# zerg_mc.net
KiCad netlist of a schematic drawn in EAGLE
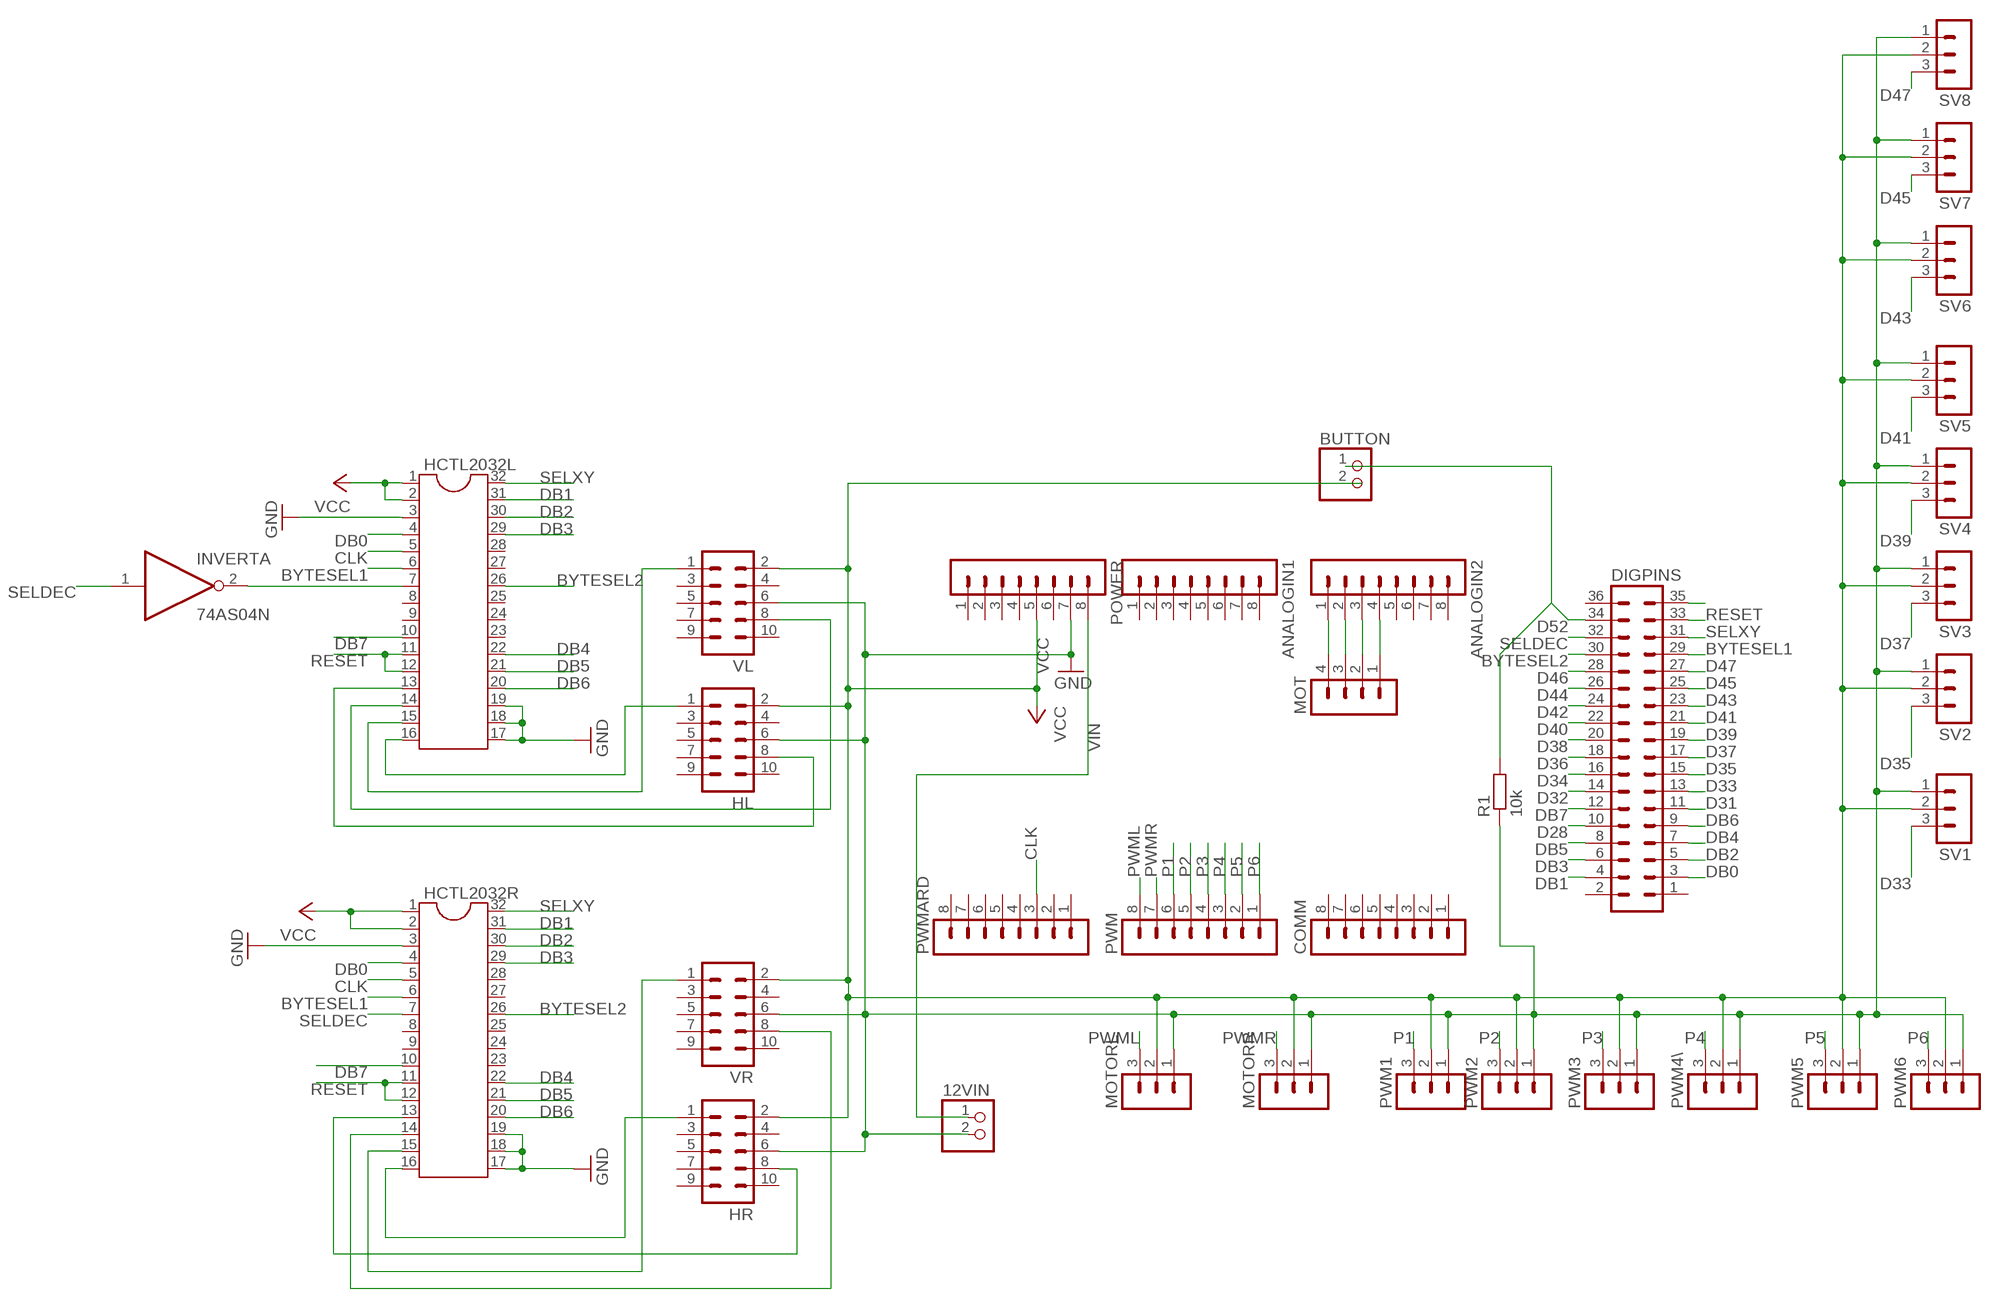
[diagram p0: schematic, sheet 1]

(export (version "E")
  (design (tool "Eeschema 10.0.6"))
  (components
    (comp (ref "12VIN")
      (value "PINHD-1X2")
      (footprint "eagle-import:1X02")
      (libsource (lib "eagle-import") (part "PINHD-1X2"))
    )
    (comp (ref "ANALOGIN1")
      (value "MA08-1")
      (footprint "eagle-import:MA08-1")
      (libsource (lib "eagle-import") (part "MA08-1"))
    )
    (comp (ref "ANALOGIN2")
      (value "MA08-1")
      (footprint "eagle-import:MA08-1")
      (libsource (lib "eagle-import") (part "MA08-1"))
    )
    (comp (ref "BUTTON")
      (value "PINHD-1X2")
      (footprint "eagle-import:1X02")
      (libsource (lib "eagle-import") (part "PINHD-1X2"))
    )
    (comp (ref "COMM")
      (value "MA08-1")
      (footprint "eagle-import:MA08-1")
      (libsource (lib "eagle-import") (part "MA08-1"))
    )
    (comp (ref "DIGPINS")
      (value "MA18-2")
      (footprint "eagle-import:MA18-2")
      (libsource (lib "eagle-import") (part "MA18-2"))
    )
    (comp (ref "HCTL2032L")
      (value "DIL32")
      (footprint "eagle-import:DIL32")
      (libsource (lib "eagle-import") (part "DIL32"))
    )
    (comp (ref "HCTL2032R")
      (value "DIL32")
      (footprint "eagle-import:DIL32")
      (libsource (lib "eagle-import") (part "DIL32"))
    )
    (comp (ref "HL")
      (value "MA05-2")
      (footprint "eagle-import:MA05-2")
      (libsource (lib "eagle-import") (part "MA05-2"))
    )
    (comp (ref "HR")
      (value "MA05-2")
      (footprint "eagle-import:MA05-2")
      (libsource (lib "eagle-import") (part "MA05-2"))
    )
    (comp (ref "INVERT")
      (value "74AS04N")
      (footprint "eagle-import:DIL14")
      (libsource (lib "eagle-import") (part "7404NAS"))
    )
    (comp (ref "MOT")
      (value "MA04-1")
      (footprint "eagle-import:MA04-1")
      (libsource (lib "eagle-import") (part "MA04-1"))
    )
    (comp (ref "MOTORL")
      (value "MA03-1")
      (footprint "eagle-import:MA03-1")
      (libsource (lib "eagle-import") (part "MA03-1"))
    )
    (comp (ref "MOTORR")
      (value "MA03-1")
      (footprint "eagle-import:MA03-1")
      (libsource (lib "eagle-import") (part "MA03-1"))
    )
    (comp (ref "POWER")
      (value "MA08-1")
      (footprint "eagle-import:MA08-1")
      (libsource (lib "eagle-import") (part "MA08-1"))
    )
    (comp (ref "PWM")
      (value "MA08-1")
      (footprint "eagle-import:MA08-1")
      (libsource (lib "eagle-import") (part "MA08-1"))
    )
    (comp (ref "PWM1")
      (value "MA03-1")
      (footprint "eagle-import:MA03-1")
      (libsource (lib "eagle-import") (part "MA03-1"))
    )
    (comp (ref "PWM2")
      (value "MA03-1")
      (footprint "eagle-import:MA03-1")
      (libsource (lib "eagle-import") (part "MA03-1"))
    )
    (comp (ref "PWM3")
      (value "MA03-1")
      (footprint "eagle-import:MA03-1")
      (libsource (lib "eagle-import") (part "MA03-1"))
    )
    (comp (ref "PWM4\\")
      (value "MA03-1")
      (footprint "eagle-import:MA03-1")
      (libsource (lib "eagle-import") (part "MA03-1"))
    )
    (comp (ref "PWM5")
      (value "MA03-1")
      (footprint "eagle-import:MA03-1")
      (libsource (lib "eagle-import") (part "MA03-1"))
    )
    (comp (ref "PWM6")
      (value "MA03-1")
      (footprint "eagle-import:MA03-1")
      (libsource (lib "eagle-import") (part "MA03-1"))
    )
    (comp (ref "PWMARD")
      (value "MA08-1")
      (footprint "eagle-import:MA08-1")
      (libsource (lib "eagle-import") (part "MA08-1"))
    )
    (comp (ref "R1")
      (value "10k")
      (footprint "eagle-import:0207_10")
      (libsource (lib "eagle-import") (part "R-EU_0207/10"))
    )
    (comp (ref "SV1")
      (value "MA03-1")
      (footprint "eagle-import:MA03-1")
      (libsource (lib "eagle-import") (part "MA03-1"))
    )
    (comp (ref "SV2")
      (value "MA03-1")
      (footprint "eagle-import:MA03-1")
      (libsource (lib "eagle-import") (part "MA03-1"))
    )
    (comp (ref "SV3")
      (value "MA03-1")
      (footprint "eagle-import:MA03-1")
      (libsource (lib "eagle-import") (part "MA03-1"))
    )
    (comp (ref "SV4")
      (value "MA03-1")
      (footprint "eagle-import:MA03-1")
      (libsource (lib "eagle-import") (part "MA03-1"))
    )
    (comp (ref "SV5")
      (value "MA03-1")
      (footprint "eagle-import:MA03-1")
      (libsource (lib "eagle-import") (part "MA03-1"))
    )
    (comp (ref "SV6")
      (value "MA03-1")
      (footprint "eagle-import:MA03-1")
      (libsource (lib "eagle-import") (part "MA03-1"))
    )
    (comp (ref "SV7")
      (value "MA03-1")
      (footprint "eagle-import:MA03-1")
      (libsource (lib "eagle-import") (part "MA03-1"))
    )
    (comp (ref "SV8")
      (value "MA03-1")
      (footprint "eagle-import:MA03-1")
      (libsource (lib "eagle-import") (part "MA03-1"))
    )
    (comp (ref "VL")
      (value "MA05-2")
      (footprint "eagle-import:MA05-2")
      (libsource (lib "eagle-import") (part "MA05-2"))
    )
    (comp (ref "VR")
      (value "MA05-2")
      (footprint "eagle-import:MA05-2")
      (libsource (lib "eagle-import") (part "MA05-2"))
    )
  )
  (nets
    (net (code "1") (name "/BYTESEL1") (class "Default")
      (node (ref "DIGPINS") (pin "29") (pinfunction "29_29") (pintype "passive"))
      (node (ref "HCTL2032L") (pin "6") (pinfunction "6_6") (pintype "passive"))
      (node (ref "HCTL2032R") (pin "6") (pinfunction "6_6") (pintype "passive"))
    )
    (net (code "2") (name "/BYTESEL2") (class "Default")
      (node (ref "DIGPINS") (pin "30") (pinfunction "30_30") (pintype "passive"))
      (node (ref "HCTL2032L") (pin "26") (pinfunction "26_26") (pintype "passive"))
      (node (ref "HCTL2032R") (pin "26") (pinfunction "26_26") (pintype "passive"))
    )
    (net (code "3") (name "/CLK") (class "Default")
      (node (ref "HCTL2032L") (pin "5") (pinfunction "5_5") (pintype "passive"))
      (node (ref "HCTL2032R") (pin "5") (pinfunction "5_5") (pintype "passive"))
      (node (ref "PWMARD") (pin "3") (pinfunction "3_3") (pintype "passive"))
    )
    (net (code "4") (name "/D28") (class "Default")
      (node (ref "DIGPINS") (pin "10") (pinfunction "10_10") (pintype "passive"))
    )
    (net (code "5") (name "/D31") (class "Default")
      (node (ref "DIGPINS") (pin "11") (pinfunction "11_11") (pintype "passive"))
    )
    (net (code "6") (name "/D32") (class "Default")
      (node (ref "DIGPINS") (pin "14") (pinfunction "14_14") (pintype "passive"))
    )
    (net (code "7") (name "/D33") (class "Default")
      (node (ref "DIGPINS") (pin "13") (pinfunction "13_13") (pintype "passive"))
      (node (ref "SV1") (pin "3") (pinfunction "3_3") (pintype "passive"))
    )
    (net (code "8") (name "/D34") (class "Default")
      (node (ref "DIGPINS") (pin "16") (pinfunction "16_16") (pintype "passive"))
    )
    (net (code "9") (name "/D35") (class "Default")
      (node (ref "DIGPINS") (pin "15") (pinfunction "15_15") (pintype "passive"))
      (node (ref "SV2") (pin "3") (pinfunction "3_3") (pintype "passive"))
    )
    (net (code "10") (name "/D36") (class "Default")
      (node (ref "DIGPINS") (pin "18") (pinfunction "18_18") (pintype "passive"))
    )
    (net (code "11") (name "/D37") (class "Default")
      (node (ref "DIGPINS") (pin "17") (pinfunction "17_17") (pintype "passive"))
      (node (ref "SV3") (pin "3") (pinfunction "3_3") (pintype "passive"))
    )
    (net (code "12") (name "/D38") (class "Default")
      (node (ref "DIGPINS") (pin "20") (pinfunction "20_20") (pintype "passive"))
    )
    (net (code "13") (name "/D39") (class "Default")
      (node (ref "DIGPINS") (pin "19") (pinfunction "19_19") (pintype "passive"))
      (node (ref "SV4") (pin "3") (pinfunction "3_3") (pintype "passive"))
    )
    (net (code "14") (name "/D40") (class "Default")
      (node (ref "DIGPINS") (pin "22") (pinfunction "22_22") (pintype "passive"))
    )
    (net (code "15") (name "/D41") (class "Default")
      (node (ref "DIGPINS") (pin "21") (pinfunction "21_21") (pintype "passive"))
      (node (ref "SV5") (pin "3") (pinfunction "3_3") (pintype "passive"))
    )
    (net (code "16") (name "/D42") (class "Default")
      (node (ref "DIGPINS") (pin "24") (pinfunction "24_24") (pintype "passive"))
    )
    (net (code "17") (name "/D43") (class "Default")
      (node (ref "DIGPINS") (pin "23") (pinfunction "23_23") (pintype "passive"))
      (node (ref "SV6") (pin "3") (pinfunction "3_3") (pintype "passive"))
    )
    (net (code "18") (name "/D44") (class "Default")
      (node (ref "DIGPINS") (pin "26") (pinfunction "26_26") (pintype "passive"))
    )
    (net (code "19") (name "/D45") (class "Default")
      (node (ref "DIGPINS") (pin "25") (pinfunction "25_25") (pintype "passive"))
      (node (ref "SV7") (pin "3") (pinfunction "3_3") (pintype "passive"))
    )
    (net (code "20") (name "/D46") (class "Default")
      (node (ref "DIGPINS") (pin "28") (pinfunction "28_28") (pintype "passive"))
    )
    (net (code "21") (name "/D47") (class "Default")
      (node (ref "DIGPINS") (pin "27") (pinfunction "27_27") (pintype "passive"))
      (node (ref "SV8") (pin "3") (pinfunction "3_3") (pintype "passive"))
    )
    (net (code "22") (name "/D52") (class "Default")
      (node (ref "BUTTON") (pin "1") (pinfunction "1_1") (pintype "passive"))
      (node (ref "DIGPINS") (pin "34") (pinfunction "34_34") (pintype "passive"))
      (node (ref "R1") (pin "2") (pinfunction "2_2") (pintype "passive"))
    )
    (net (code "23") (name "/DB0") (class "Default")
      (node (ref "DIGPINS") (pin "3") (pinfunction "3_3") (pintype "passive"))
      (node (ref "HCTL2032L") (pin "4") (pinfunction "4_4") (pintype "passive"))
      (node (ref "HCTL2032R") (pin "4") (pinfunction "4_4") (pintype "passive"))
    )
    (net (code "24") (name "/DB1") (class "Default")
      (node (ref "DIGPINS") (pin "4") (pinfunction "4_4") (pintype "passive"))
      (node (ref "HCTL2032L") (pin "31") (pinfunction "31_31") (pintype "passive"))
      (node (ref "HCTL2032R") (pin "31") (pinfunction "31_31") (pintype "passive"))
    )
    (net (code "25") (name "/DB2") (class "Default")
      (node (ref "DIGPINS") (pin "5") (pinfunction "5_5") (pintype "passive"))
      (node (ref "HCTL2032L") (pin "30") (pinfunction "30_30") (pintype "passive"))
      (node (ref "HCTL2032R") (pin "30") (pinfunction "30_30") (pintype "passive"))
    )
    (net (code "26") (name "/DB3") (class "Default")
      (node (ref "DIGPINS") (pin "6") (pinfunction "6_6") (pintype "passive"))
      (node (ref "HCTL2032L") (pin "29") (pinfunction "29_29") (pintype "passive"))
      (node (ref "HCTL2032R") (pin "29") (pinfunction "29_29") (pintype "passive"))
    )
    (net (code "27") (name "/DB4") (class "Default")
      (node (ref "DIGPINS") (pin "7") (pinfunction "7_7") (pintype "passive"))
      (node (ref "HCTL2032L") (pin "22") (pinfunction "22_22") (pintype "passive"))
      (node (ref "HCTL2032R") (pin "22") (pinfunction "22_22") (pintype "passive"))
    )
    (net (code "28") (name "/DB5") (class "Default")
      (node (ref "DIGPINS") (pin "8") (pinfunction "8_8") (pintype "passive"))
      (node (ref "HCTL2032L") (pin "21") (pinfunction "21_21") (pintype "passive"))
      (node (ref "HCTL2032R") (pin "21") (pinfunction "21_21") (pintype "passive"))
    )
    (net (code "29") (name "/DB6") (class "Default")
      (node (ref "DIGPINS") (pin "9") (pinfunction "9_9") (pintype "passive"))
      (node (ref "HCTL2032L") (pin "20") (pinfunction "20_20") (pintype "passive"))
      (node (ref "HCTL2032R") (pin "20") (pinfunction "20_20") (pintype "passive"))
    )
    (net (code "30") (name "/DB7") (class "Default")
      (node (ref "DIGPINS") (pin "12") (pinfunction "12_12") (pintype "passive"))
      (node (ref "HCTL2032L") (pin "10") (pinfunction "10_10") (pintype "passive"))
      (node (ref "HCTL2032R") (pin "10") (pinfunction "10_10") (pintype "passive"))
    )
    (net (code "31") (name "/P1") (class "Default")
      (node (ref "PWM") (pin "6") (pinfunction "6_6") (pintype "passive"))
      (node (ref "PWM1") (pin "3") (pinfunction "3_3") (pintype "passive"))
    )
    (net (code "32") (name "/P2") (class "Default")
      (node (ref "PWM") (pin "5") (pinfunction "5_5") (pintype "passive"))
      (node (ref "PWM2") (pin "3") (pinfunction "3_3") (pintype "passive"))
    )
    (net (code "33") (name "/P3") (class "Default")
      (node (ref "PWM") (pin "4") (pinfunction "4_4") (pintype "passive"))
      (node (ref "PWM3") (pin "3") (pinfunction "3_3") (pintype "passive"))
    )
    (net (code "34") (name "/P4") (class "Default")
      (node (ref "PWM") (pin "3") (pinfunction "3_3") (pintype "passive"))
      (node (ref "PWM4\\") (pin "3") (pinfunction "3_3") (pintype "passive"))
    )
    (net (code "35") (name "/P5") (class "Default")
      (node (ref "PWM") (pin "2") (pinfunction "2_2") (pintype "passive"))
      (node (ref "PWM5") (pin "3") (pinfunction "3_3") (pintype "passive"))
    )
    (net (code "36") (name "/P6") (class "Default")
      (node (ref "PWM") (pin "1") (pinfunction "1_1") (pintype "passive"))
      (node (ref "PWM6") (pin "3") (pinfunction "3_3") (pintype "passive"))
    )
    (net (code "37") (name "/PWML") (class "Default")
      (node (ref "MOTORL") (pin "3") (pinfunction "3_3") (pintype "passive"))
      (node (ref "PWM") (pin "8") (pinfunction "8_8") (pintype "passive"))
    )
    (net (code "38") (name "/PWMR") (class "Default")
      (node (ref "MOTORR") (pin "3") (pinfunction "3_3") (pintype "passive"))
      (node (ref "PWM") (pin "7") (pinfunction "7_7") (pintype "passive"))
    )
    (net (code "39") (name "/RESET") (class "Default")
      (node (ref "DIGPINS") (pin "33") (pinfunction "33_33") (pintype "passive"))
      (node (ref "HCTL2032L") (pin "11") (pinfunction "11_11") (pintype "passive"))
      (node (ref "HCTL2032L") (pin "12") (pinfunction "12_12") (pintype "passive"))
      (node (ref "HCTL2032R") (pin "11") (pinfunction "11_11") (pintype "passive"))
      (node (ref "HCTL2032R") (pin "12") (pinfunction "12_12") (pintype "passive"))
    )
    (net (code "40") (name "/SELDEC") (class "Default")
      (node (ref "DIGPINS") (pin "32") (pinfunction "32_32") (pintype "passive"))
      (node (ref "HCTL2032R") (pin "7") (pinfunction "7_7") (pintype "passive"))
      (node (ref "INVERT") (pin "1") (pinfunction "I_1") (pintype "input"))
    )
    (net (code "41") (name "/SELXY") (class "Default")
      (node (ref "DIGPINS") (pin "31") (pinfunction "31_31") (pintype "passive"))
      (node (ref "HCTL2032L") (pin "32") (pinfunction "32_32") (pintype "passive"))
      (node (ref "HCTL2032R") (pin "32") (pinfunction "32_32") (pintype "passive"))
    )
    (net (code "42") (name "/VIN") (class "Default")
      (node (ref "12VIN") (pin "1") (pinfunction "1_1") (pintype "passive"))
      (node (ref "POWER") (pin "8") (pinfunction "8_8") (pintype "passive"))
    )
    (net (code "43") (name "GND") (class "Default")
      (node (ref "12VIN") (pin "2") (pinfunction "2_2") (pintype "passive"))
      (node (ref "HCTL2032L") (pin "17") (pinfunction "17_17") (pintype "passive"))
      (node (ref "HCTL2032L") (pin "18") (pinfunction "18_18") (pintype "passive"))
      (node (ref "HCTL2032L") (pin "19") (pinfunction "19_19") (pintype "passive"))
      (node (ref "HCTL2032L") (pin "3") (pinfunction "3_3") (pintype "passive"))
      (node (ref "HCTL2032R") (pin "17") (pinfunction "17_17") (pintype "passive"))
      (node (ref "HCTL2032R") (pin "18") (pinfunction "18_18") (pintype "passive"))
      (node (ref "HCTL2032R") (pin "19") (pinfunction "19_19") (pintype "passive"))
      (node (ref "HCTL2032R") (pin "3") (pinfunction "3_3") (pintype "passive"))
      (node (ref "HL") (pin "6") (pinfunction "6_6") (pintype "passive"))
      (node (ref "HR") (pin "6") (pinfunction "6_6") (pintype "passive"))
      (node (ref "MOTORL") (pin "1") (pinfunction "1_1") (pintype "passive"))
      (node (ref "MOTORR") (pin "1") (pinfunction "1_1") (pintype "passive"))
      (node (ref "POWER") (pin "7") (pinfunction "7_7") (pintype "passive"))
      (node (ref "PWM1") (pin "1") (pinfunction "1_1") (pintype "passive"))
      (node (ref "PWM2") (pin "1") (pinfunction "1_1") (pintype "passive"))
      (node (ref "PWM3") (pin "1") (pinfunction "1_1") (pintype "passive"))
      (node (ref "PWM4\\") (pin "1") (pinfunction "1_1") (pintype "passive"))
      (node (ref "PWM5") (pin "1") (pinfunction "1_1") (pintype "passive"))
      (node (ref "PWM6") (pin "1") (pinfunction "1_1") (pintype "passive"))
      (node (ref "R1") (pin "1") (pinfunction "1_1") (pintype "passive"))
      (node (ref "SV1") (pin "1") (pinfunction "1_1") (pintype "passive"))
      (node (ref "SV2") (pin "1") (pinfunction "1_1") (pintype "passive"))
      (node (ref "SV3") (pin "1") (pinfunction "1_1") (pintype "passive"))
      (node (ref "SV4") (pin "1") (pinfunction "1_1") (pintype "passive"))
      (node (ref "SV5") (pin "1") (pinfunction "1_1") (pintype "passive"))
      (node (ref "SV6") (pin "1") (pinfunction "1_1") (pintype "passive"))
      (node (ref "SV7") (pin "1") (pinfunction "1_1") (pintype "passive"))
      (node (ref "SV8") (pin "1") (pinfunction "1_1") (pintype "passive"))
      (node (ref "VL") (pin "6") (pinfunction "6_6") (pintype "passive"))
      (node (ref "VR") (pin "6") (pinfunction "6_6") (pintype "passive"))
    )
    (net (code "44") (name "Net-(ANALOGIN2-Pad1)") (class "Default")
      (node (ref "ANALOGIN2") (pin "1") (pinfunction "1_1") (pintype "passive"))
      (node (ref "MOT") (pin "4") (pinfunction "4_4") (pintype "passive"))
    )
    (net (code "45") (name "Net-(ANALOGIN2-Pad2)") (class "Default")
      (node (ref "ANALOGIN2") (pin "2") (pinfunction "2_2") (pintype "passive"))
      (node (ref "MOT") (pin "3") (pinfunction "3_3") (pintype "passive"))
    )
    (net (code "46") (name "Net-(ANALOGIN2-Pad3)") (class "Default")
      (node (ref "ANALOGIN2") (pin "3") (pinfunction "3_3") (pintype "passive"))
      (node (ref "MOT") (pin "2") (pinfunction "2_2") (pintype "passive"))
    )
    (net (code "47") (name "Net-(ANALOGIN2-Pad4)") (class "Default")
      (node (ref "ANALOGIN2") (pin "4") (pinfunction "4_4") (pintype "passive"))
      (node (ref "MOT") (pin "1") (pinfunction "1_1") (pintype "passive"))
    )
    (net (code "48") (name "Net-(HCTL2032L-Pad13)") (class "Default")
      (node (ref "HCTL2032L") (pin "13") (pinfunction "13_13") (pintype "passive"))
      (node (ref "HL") (pin "8") (pinfunction "8_8") (pintype "passive"))
    )
    (net (code "49") (name "Net-(HCTL2032L-Pad14)") (class "Default")
      (node (ref "HCTL2032L") (pin "14") (pinfunction "14_14") (pintype "passive"))
      (node (ref "VL") (pin "8") (pinfunction "8_8") (pintype "passive"))
    )
    (net (code "50") (name "Net-(HCTL2032L-Pad15)") (class "Default")
      (node (ref "HCTL2032L") (pin "15") (pinfunction "15_15") (pintype "passive"))
      (node (ref "VL") (pin "1") (pinfunction "1_1") (pintype "passive"))
    )
    (net (code "51") (name "Net-(HCTL2032L-Pad16)") (class "Default")
      (node (ref "HCTL2032L") (pin "16") (pinfunction "16_16") (pintype "passive"))
      (node (ref "HL") (pin "1") (pinfunction "1_1") (pintype "passive"))
    )
    (net (code "52") (name "Net-(HCTL2032R-Pad13)") (class "Default")
      (node (ref "HCTL2032R") (pin "13") (pinfunction "13_13") (pintype "passive"))
      (node (ref "HR") (pin "8") (pinfunction "8_8") (pintype "passive"))
    )
    (net (code "53") (name "Net-(HCTL2032R-Pad14)") (class "Default")
      (node (ref "HCTL2032R") (pin "14") (pinfunction "14_14") (pintype "passive"))
      (node (ref "VR") (pin "8") (pinfunction "8_8") (pintype "passive"))
    )
    (net (code "54") (name "Net-(HCTL2032R-Pad15)") (class "Default")
      (node (ref "HCTL2032R") (pin "15") (pinfunction "15_15") (pintype "passive"))
      (node (ref "VR") (pin "1") (pinfunction "1_1") (pintype "passive"))
    )
    (net (code "55") (name "Net-(HCTL2032R-Pad16)") (class "Default")
      (node (ref "HCTL2032R") (pin "16") (pinfunction "16_16") (pintype "passive"))
      (node (ref "HR") (pin "1") (pinfunction "1_1") (pintype "passive"))
    )
    (net (code "56") (name "Net-(INVERTA-O)") (class "Default")
      (node (ref "HCTL2032L") (pin "7") (pinfunction "7_7") (pintype "passive"))
      (node (ref "INVERT") (pin "2") (pinfunction "O_2") (pintype "output"))
    )
    (net (code "57") (name "VCC") (class "Default")
      (node (ref "HCTL2032L") (pin "1") (pinfunction "1_1") (pintype "passive"))
      (node (ref "HCTL2032L") (pin "2") (pinfunction "2_2") (pintype "passive"))
      (node (ref "HCTL2032R") (pin "1") (pinfunction "1_1") (pintype "passive"))
      (node (ref "HCTL2032R") (pin "2") (pinfunction "2_2") (pintype "passive"))
      (node (ref "HL") (pin "2") (pinfunction "2_2") (pintype "passive"))
      (node (ref "HR") (pin "2") (pinfunction "2_2") (pintype "passive"))
      (node (ref "MOTORL") (pin "2") (pinfunction "2_2") (pintype "passive"))
      (node (ref "MOTORR") (pin "2") (pinfunction "2_2") (pintype "passive"))
      (node (ref "POWER") (pin "5") (pinfunction "5_5") (pintype "passive"))
      (node (ref "PWM1") (pin "2") (pinfunction "2_2") (pintype "passive"))
      (node (ref "PWM2") (pin "2") (pinfunction "2_2") (pintype "passive"))
      (node (ref "PWM3") (pin "2") (pinfunction "2_2") (pintype "passive"))
      (node (ref "PWM4\\") (pin "2") (pinfunction "2_2") (pintype "passive"))
      (node (ref "PWM5") (pin "2") (pinfunction "2_2") (pintype "passive"))
      (node (ref "PWM6") (pin "2") (pinfunction "2_2") (pintype "passive"))
      (node (ref "SV1") (pin "2") (pinfunction "2_2") (pintype "passive"))
      (node (ref "SV2") (pin "2") (pinfunction "2_2") (pintype "passive"))
      (node (ref "SV3") (pin "2") (pinfunction "2_2") (pintype "passive"))
      (node (ref "SV4") (pin "2") (pinfunction "2_2") (pintype "passive"))
      (node (ref "SV5") (pin "2") (pinfunction "2_2") (pintype "passive"))
      (node (ref "SV6") (pin "2") (pinfunction "2_2") (pintype "passive"))
      (node (ref "SV7") (pin "2") (pinfunction "2_2") (pintype "passive"))
      (node (ref "SV8") (pin "2") (pinfunction "2_2") (pintype "passive"))
      (node (ref "VL") (pin "2") (pinfunction "2_2") (pintype "passive"))
      (node (ref "VR") (pin "2") (pinfunction "2_2") (pintype "passive"))
    )
    (net (code "58") (name "unconnected-(ANALOGIN1-Pad1)") (class "Default")
      (node (ref "ANALOGIN1") (pin "1") (pinfunction "1_1") (pintype "passive"))
    )
    (net (code "59") (name "unconnected-(ANALOGIN1-Pad2)") (class "Default")
      (node (ref "ANALOGIN1") (pin "2") (pinfunction "2_2") (pintype "passive"))
    )
    (net (code "60") (name "unconnected-(ANALOGIN1-Pad3)") (class "Default")
      (node (ref "ANALOGIN1") (pin "3") (pinfunction "3_3") (pintype "passive"))
    )
    (net (code "61") (name "unconnected-(ANALOGIN1-Pad4)") (class "Default")
      (node (ref "ANALOGIN1") (pin "4") (pinfunction "4_4") (pintype "passive"))
    )
    (net (code "62") (name "unconnected-(ANALOGIN1-Pad5)") (class "Default")
      (node (ref "ANALOGIN1") (pin "5") (pinfunction "5_5") (pintype "passive"))
    )
    (net (code "63") (name "unconnected-(ANALOGIN1-Pad6)") (class "Default")
      (node (ref "ANALOGIN1") (pin "6") (pinfunction "6_6") (pintype "passive"))
    )
    (net (code "64") (name "unconnected-(ANALOGIN1-Pad7)") (class "Default")
      (node (ref "ANALOGIN1") (pin "7") (pinfunction "7_7") (pintype "passive"))
    )
    (net (code "65") (name "unconnected-(ANALOGIN1-Pad8)") (class "Default")
      (node (ref "ANALOGIN1") (pin "8") (pinfunction "8_8") (pintype "passive"))
    )
    (net (code "66") (name "unconnected-(ANALOGIN2-Pad5)") (class "Default")
      (node (ref "ANALOGIN2") (pin "5") (pinfunction "5_5") (pintype "passive"))
    )
    (net (code "67") (name "unconnected-(ANALOGIN2-Pad6)") (class "Default")
      (node (ref "ANALOGIN2") (pin "6") (pinfunction "6_6") (pintype "passive"))
    )
    (net (code "68") (name "unconnected-(ANALOGIN2-Pad7)") (class "Default")
      (node (ref "ANALOGIN2") (pin "7") (pinfunction "7_7") (pintype "passive"))
    )
    (net (code "69") (name "unconnected-(ANALOGIN2-Pad8)") (class "Default")
      (node (ref "ANALOGIN2") (pin "8") (pinfunction "8_8") (pintype "passive"))
    )
    (net (code "70") (name "unconnected-(BUTTON-Pad2)") (class "Default")
      (node (ref "BUTTON") (pin "2") (pinfunction "2_2") (pintype "passive"))
    )
    (net (code "71") (name "unconnected-(COMM-Pad1)") (class "Default")
      (node (ref "COMM") (pin "1") (pinfunction "1_1") (pintype "passive"))
    )
    (net (code "72") (name "unconnected-(COMM-Pad2)") (class "Default")
      (node (ref "COMM") (pin "2") (pinfunction "2_2") (pintype "passive"))
    )
    (net (code "73") (name "unconnected-(COMM-Pad3)") (class "Default")
      (node (ref "COMM") (pin "3") (pinfunction "3_3") (pintype "passive"))
    )
    (net (code "74") (name "unconnected-(COMM-Pad4)") (class "Default")
      (node (ref "COMM") (pin "4") (pinfunction "4_4") (pintype "passive"))
    )
    (net (code "75") (name "unconnected-(COMM-Pad5)") (class "Default")
      (node (ref "COMM") (pin "5") (pinfunction "5_5") (pintype "passive"))
    )
    (net (code "76") (name "unconnected-(COMM-Pad6)") (class "Default")
      (node (ref "COMM") (pin "6") (pinfunction "6_6") (pintype "passive"))
    )
    (net (code "77") (name "unconnected-(COMM-Pad7)") (class "Default")
      (node (ref "COMM") (pin "7") (pinfunction "7_7") (pintype "passive"))
    )
    (net (code "78") (name "unconnected-(COMM-Pad8)") (class "Default")
      (node (ref "COMM") (pin "8") (pinfunction "8_8") (pintype "passive"))
    )
    (net (code "79") (name "unconnected-(DIGPINS-Pad1)") (class "Default")
      (node (ref "DIGPINS") (pin "1") (pinfunction "1_1") (pintype "passive"))
    )
    (net (code "80") (name "unconnected-(DIGPINS-Pad2)") (class "Default")
      (node (ref "DIGPINS") (pin "2") (pinfunction "2_2") (pintype "passive"))
    )
    (net (code "81") (name "unconnected-(DIGPINS-Pad35)") (class "Default")
      (node (ref "DIGPINS") (pin "35") (pinfunction "35_35") (pintype "passive"))
    )
    (net (code "82") (name "unconnected-(DIGPINS-Pad36)") (class "Default")
      (node (ref "DIGPINS") (pin "36") (pinfunction "36_36") (pintype "passive"))
    )
    (net (code "83") (name "unconnected-(HCTL2032L-Pad8)") (class "Default")
      (node (ref "HCTL2032L") (pin "8") (pinfunction "8_8") (pintype "passive"))
    )
    (net (code "84") (name "unconnected-(HCTL2032L-Pad9)") (class "Default")
      (node (ref "HCTL2032L") (pin "9") (pinfunction "9_9") (pintype "passive"))
    )
    (net (code "85") (name "unconnected-(HCTL2032L-Pad23)") (class "Default")
      (node (ref "HCTL2032L") (pin "23") (pinfunction "23_23") (pintype "passive"))
    )
    (net (code "86") (name "unconnected-(HCTL2032L-Pad24)") (class "Default")
      (node (ref "HCTL2032L") (pin "24") (pinfunction "24_24") (pintype "passive"))
    )
    (net (code "87") (name "unconnected-(HCTL2032L-Pad25)") (class "Default")
      (node (ref "HCTL2032L") (pin "25") (pinfunction "25_25") (pintype "passive"))
    )
    (net (code "88") (name "unconnected-(HCTL2032L-Pad27)") (class "Default")
      (node (ref "HCTL2032L") (pin "27") (pinfunction "27_27") (pintype "passive"))
    )
    (net (code "89") (name "unconnected-(HCTL2032L-Pad28)") (class "Default")
      (node (ref "HCTL2032L") (pin "28") (pinfunction "28_28") (pintype "passive"))
    )
    (net (code "90") (name "unconnected-(HCTL2032R-Pad8)") (class "Default")
      (node (ref "HCTL2032R") (pin "8") (pinfunction "8_8") (pintype "passive"))
    )
    (net (code "91") (name "unconnected-(HCTL2032R-Pad9)") (class "Default")
      (node (ref "HCTL2032R") (pin "9") (pinfunction "9_9") (pintype "passive"))
    )
    (net (code "92") (name "unconnected-(HCTL2032R-Pad23)") (class "Default")
      (node (ref "HCTL2032R") (pin "23") (pinfunction "23_23") (pintype "passive"))
    )
    (net (code "93") (name "unconnected-(HCTL2032R-Pad24)") (class "Default")
      (node (ref "HCTL2032R") (pin "24") (pinfunction "24_24") (pintype "passive"))
    )
    (net (code "94") (name "unconnected-(HCTL2032R-Pad25)") (class "Default")
      (node (ref "HCTL2032R") (pin "25") (pinfunction "25_25") (pintype "passive"))
    )
    (net (code "95") (name "unconnected-(HCTL2032R-Pad27)") (class "Default")
      (node (ref "HCTL2032R") (pin "27") (pinfunction "27_27") (pintype "passive"))
    )
    (net (code "96") (name "unconnected-(HCTL2032R-Pad28)") (class "Default")
      (node (ref "HCTL2032R") (pin "28") (pinfunction "28_28") (pintype "passive"))
    )
    (net (code "97") (name "unconnected-(HL-Pad3)") (class "Default")
      (node (ref "HL") (pin "3") (pinfunction "3_3") (pintype "passive"))
    )
    (net (code "98") (name "unconnected-(HL-Pad4)") (class "Default")
      (node (ref "HL") (pin "4") (pinfunction "4_4") (pintype "passive"))
    )
    (net (code "99") (name "unconnected-(HL-Pad5)") (class "Default")
      (node (ref "HL") (pin "5") (pinfunction "5_5") (pintype "passive"))
    )
    (net (code "100") (name "unconnected-(HL-Pad7)") (class "Default")
      (node (ref "HL") (pin "7") (pinfunction "7_7") (pintype "passive"))
    )
    (net (code "101") (name "unconnected-(HL-Pad9)") (class "Default")
      (node (ref "HL") (pin "9") (pinfunction "9_9") (pintype "passive"))
    )
    (net (code "102") (name "unconnected-(HL-Pad10)") (class "Default")
      (node (ref "HL") (pin "10") (pinfunction "10_10") (pintype "passive"))
    )
    (net (code "103") (name "unconnected-(HR-Pad3)") (class "Default")
      (node (ref "HR") (pin "3") (pinfunction "3_3") (pintype "passive"))
    )
    (net (code "104") (name "unconnected-(HR-Pad4)") (class "Default")
      (node (ref "HR") (pin "4") (pinfunction "4_4") (pintype "passive"))
    )
    (net (code "105") (name "unconnected-(HR-Pad5)") (class "Default")
      (node (ref "HR") (pin "5") (pinfunction "5_5") (pintype "passive"))
    )
    (net (code "106") (name "unconnected-(HR-Pad7)") (class "Default")
      (node (ref "HR") (pin "7") (pinfunction "7_7") (pintype "passive"))
    )
    (net (code "107") (name "unconnected-(HR-Pad9)") (class "Default")
      (node (ref "HR") (pin "9") (pinfunction "9_9") (pintype "passive"))
    )
    (net (code "108") (name "unconnected-(HR-Pad10)") (class "Default")
      (node (ref "HR") (pin "10") (pinfunction "10_10") (pintype "passive"))
    )
    (net (code "109") (name "unconnected-(POWER-Pad1)") (class "Default")
      (node (ref "POWER") (pin "1") (pinfunction "1_1") (pintype "passive"))
    )
    (net (code "110") (name "unconnected-(POWER-Pad2)") (class "Default")
      (node (ref "POWER") (pin "2") (pinfunction "2_2") (pintype "passive"))
    )
    (net (code "111") (name "unconnected-(POWER-Pad3)") (class "Default")
      (node (ref "POWER") (pin "3") (pinfunction "3_3") (pintype "passive"))
    )
    (net (code "112") (name "unconnected-(POWER-Pad4)") (class "Default")
      (node (ref "POWER") (pin "4") (pinfunction "4_4") (pintype "passive"))
    )
    (net (code "113") (name "unconnected-(POWER-Pad6)") (class "Default")
      (node (ref "POWER") (pin "6") (pinfunction "6_6") (pintype "passive"))
    )
    (net (code "114") (name "unconnected-(PWMARD-Pad1)") (class "Default")
      (node (ref "PWMARD") (pin "1") (pinfunction "1_1") (pintype "passive"))
    )
    (net (code "115") (name "unconnected-(PWMARD-Pad2)") (class "Default")
      (node (ref "PWMARD") (pin "2") (pinfunction "2_2") (pintype "passive"))
    )
    (net (code "116") (name "unconnected-(PWMARD-Pad4)") (class "Default")
      (node (ref "PWMARD") (pin "4") (pinfunction "4_4") (pintype "passive"))
    )
    (net (code "117") (name "unconnected-(PWMARD-Pad5)") (class "Default")
      (node (ref "PWMARD") (pin "5") (pinfunction "5_5") (pintype "passive"))
    )
    (net (code "118") (name "unconnected-(PWMARD-Pad6)") (class "Default")
      (node (ref "PWMARD") (pin "6") (pinfunction "6_6") (pintype "passive"))
    )
    (net (code "119") (name "unconnected-(PWMARD-Pad7)") (class "Default")
      (node (ref "PWMARD") (pin "7") (pinfunction "7_7") (pintype "passive"))
    )
    (net (code "120") (name "unconnected-(PWMARD-Pad8)") (class "Default")
      (node (ref "PWMARD") (pin "8") (pinfunction "8_8") (pintype "passive"))
    )
    (net (code "121") (name "unconnected-(VL-Pad3)") (class "Default")
      (node (ref "VL") (pin "3") (pinfunction "3_3") (pintype "passive"))
    )
    (net (code "122") (name "unconnected-(VL-Pad4)") (class "Default")
      (node (ref "VL") (pin "4") (pinfunction "4_4") (pintype "passive"))
    )
    (net (code "123") (name "unconnected-(VL-Pad5)") (class "Default")
      (node (ref "VL") (pin "5") (pinfunction "5_5") (pintype "passive"))
    )
    (net (code "124") (name "unconnected-(VL-Pad7)") (class "Default")
      (node (ref "VL") (pin "7") (pinfunction "7_7") (pintype "passive"))
    )
    (net (code "125") (name "unconnected-(VL-Pad9)") (class "Default")
      (node (ref "VL") (pin "9") (pinfunction "9_9") (pintype "passive"))
    )
    (net (code "126") (name "unconnected-(VL-Pad10)") (class "Default")
      (node (ref "VL") (pin "10") (pinfunction "10_10") (pintype "passive"))
    )
    (net (code "127") (name "unconnected-(VR-Pad3)") (class "Default")
      (node (ref "VR") (pin "3") (pinfunction "3_3") (pintype "passive"))
    )
    (net (code "128") (name "unconnected-(VR-Pad4)") (class "Default")
      (node (ref "VR") (pin "4") (pinfunction "4_4") (pintype "passive"))
    )
    (net (code "129") (name "unconnected-(VR-Pad5)") (class "Default")
      (node (ref "VR") (pin "5") (pinfunction "5_5") (pintype "passive"))
    )
    (net (code "130") (name "unconnected-(VR-Pad7)") (class "Default")
      (node (ref "VR") (pin "7") (pinfunction "7_7") (pintype "passive"))
    )
    (net (code "131") (name "unconnected-(VR-Pad9)") (class "Default")
      (node (ref "VR") (pin "9") (pinfunction "9_9") (pintype "passive"))
    )
    (net (code "132") (name "unconnected-(VR-Pad10)") (class "Default")
      (node (ref "VR") (pin "10") (pinfunction "10_10") (pintype "passive"))
    )
  )
)
